# Protoboard.net
KiCad netlist of a schematic drawn in EAGLE
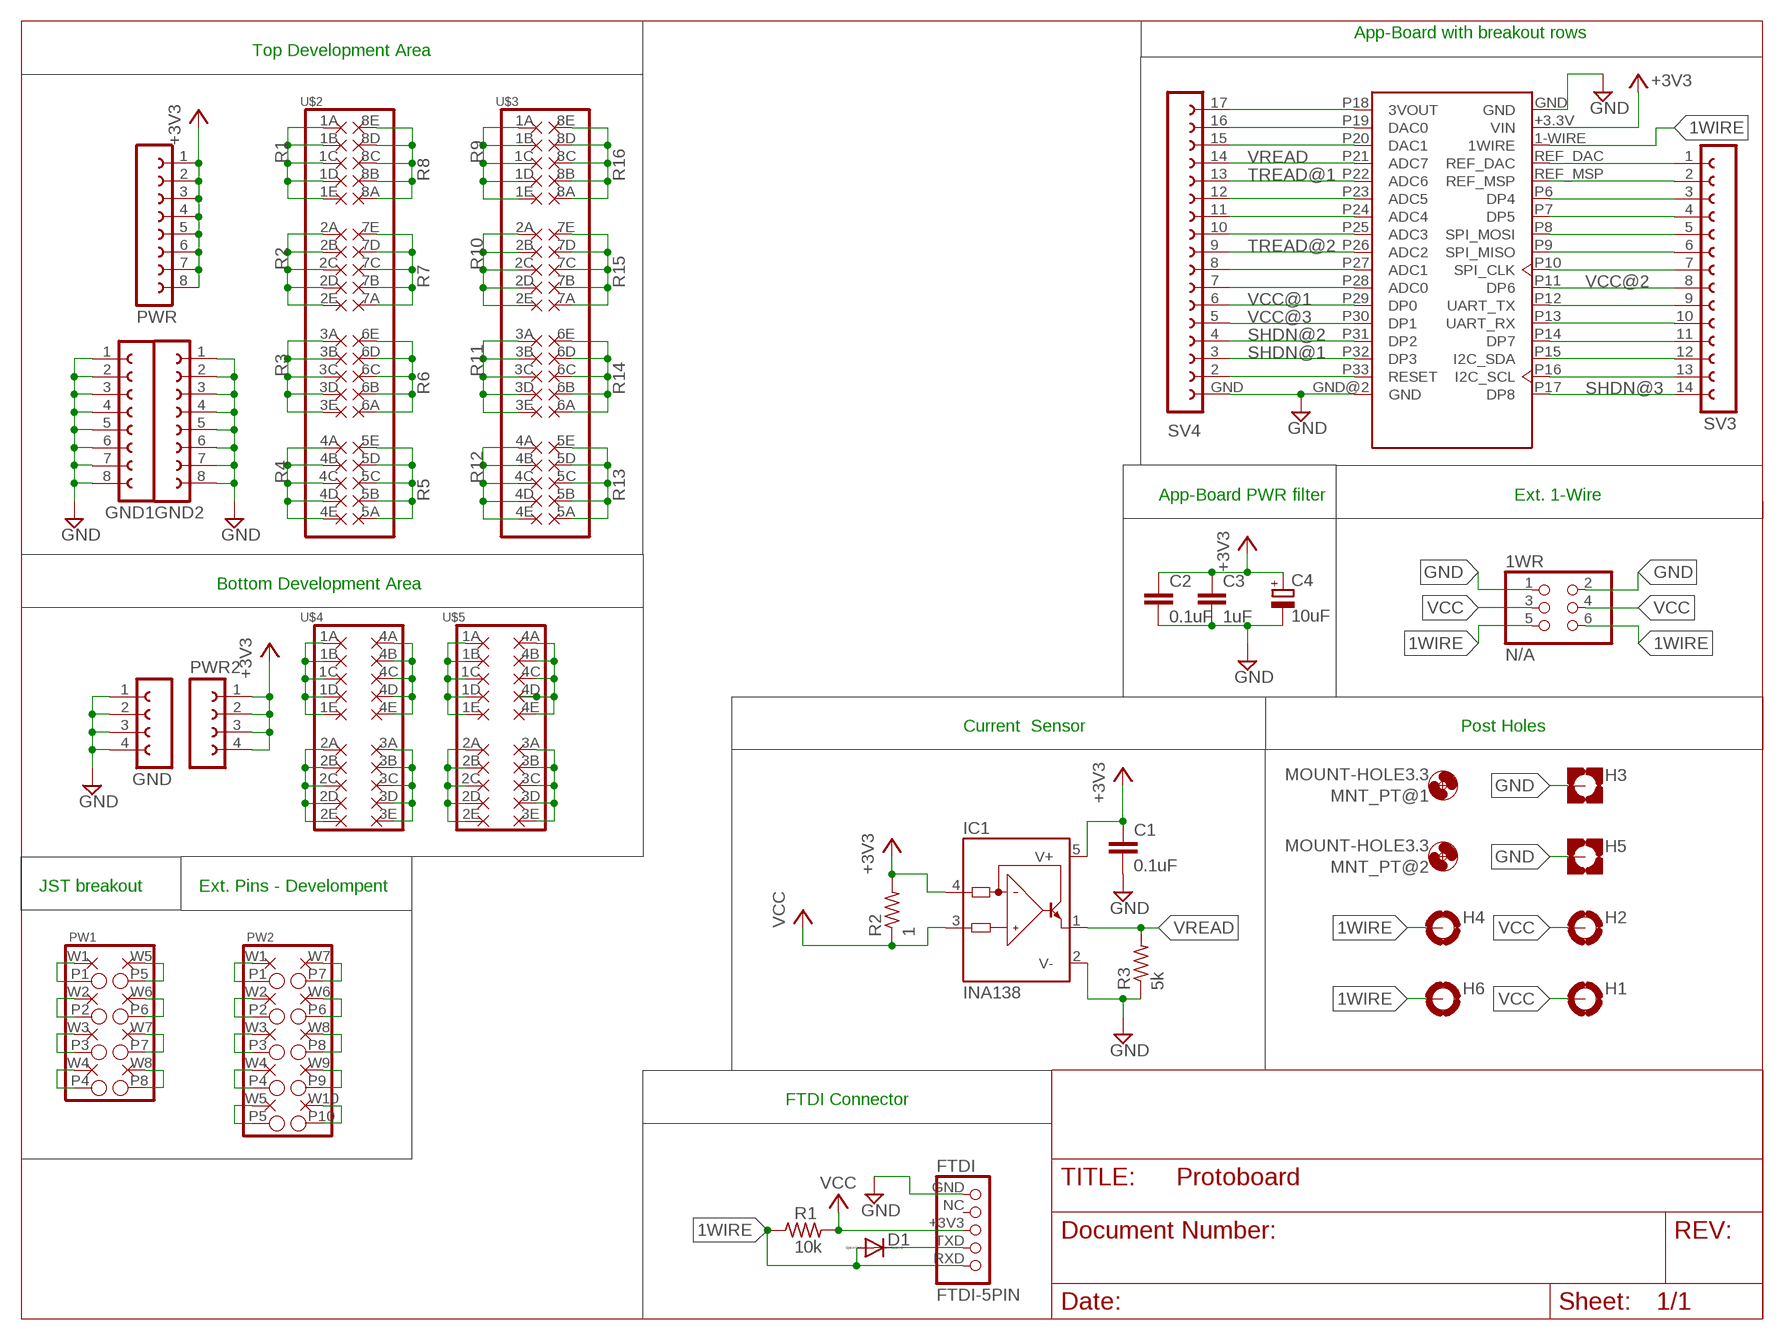
[diagram p0: schematic, sheet 1]

(export (version "E")
  (design (tool "Eeschema 10.0.6"))
  (components
    (comp (ref "1WR")
      (value "N/A")
      (footprint "eagle-import:2X03")
      (libsource (lib "eagle-import") (part "PINHD-2X3"))
    )
    (comp (ref "C1")
      (value "0.1uF")
      (footprint "eagle-import:C0603")
      (libsource (lib "eagle-import") (part "C-EUC0603"))
    )
    (comp (ref "C2")
      (value "0.1uF")
      (footprint "eagle-import:C0603")
      (libsource (lib "eagle-import") (part "C-EUC0603"))
    )
    (comp (ref "C3")
      (value "1uF")
      (footprint "eagle-import:C0603")
      (libsource (lib "eagle-import") (part "C-EUC0603"))
    )
    (comp (ref "C4")
      (value "10uF")
      (footprint "eagle-import:SMC_B")
      (libsource (lib "eagle-import") (part "CPOL-EUSMCB"))
    )
    (comp (ref "D1")
      (value "1N4148DO35-7")
      (footprint "eagle-import:DO35-7")
      (libsource (lib "eagle-import") (part "1N4148DO35-7"))
    )
    (comp (ref "FTDI")
      (value "FTDI-5PIN")
      (footprint "eagle-import:1X05")
      (libsource (lib "eagle-import") (part "FTDI-5PIN"))
    )
    (comp (ref "GND")
      (value "FE04-1-GND")
      (footprint "eagle-import:FE04-GND")
      (libsource (lib "eagle-import") (part "FE04-1-GND"))
    )
    (comp (ref "GND1")
      (value "FE08-1-GND")
      (footprint "eagle-import:FE08-GND")
      (libsource (lib "eagle-import") (part "FE08-1-GND"))
    )
    (comp (ref "GND2")
      (value "FE08-1-GND")
      (footprint "eagle-import:FE08-GND")
      (libsource (lib "eagle-import") (part "FE08-1-GND"))
    )
    (comp (ref "H1")
      (value "MOUNT-PAD-ROUND3.3")
      (footprint "eagle-import:3,3-PAD")
      (libsource (lib "eagle-import") (part "MOUNT-PAD-ROUND3.3"))
    )
    (comp (ref "H2")
      (value "MOUNT-PAD-ROUND3.3")
      (footprint "eagle-import:3,3-PAD")
      (libsource (lib "eagle-import") (part "MOUNT-PAD-ROUND3.3"))
    )
    (comp (ref "H3")
      (value "MOUNT-PAD-SQUARE3.3")
      (footprint "eagle-import:3,3-PAD-SQUARE")
      (libsource (lib "eagle-import") (part "MOUNT-PAD-SQUARE3.3"))
    )
    (comp (ref "H4")
      (value "MOUNT-PAD-ROUND3.3")
      (footprint "eagle-import:3,3-PAD")
      (libsource (lib "eagle-import") (part "MOUNT-PAD-ROUND3.3"))
    )
    (comp (ref "H5")
      (value "MOUNT-PAD-SQUARE3.3")
      (footprint "eagle-import:3,3-PAD-SQUARE")
      (libsource (lib "eagle-import") (part "MOUNT-PAD-SQUARE3.3"))
    )
    (comp (ref "H6")
      (value "MOUNT-PAD-ROUND3.3")
      (footprint "eagle-import:3,3-PAD")
      (libsource (lib "eagle-import") (part "MOUNT-PAD-ROUND3.3"))
    )
    (comp (ref "IC1")
      (value "INA138")
      (footprint "eagle-import:SOT23-5")
      (fields (field (name "MF") "TEXAS INSTRUMENTS") (field (name "MPN") "INA138NA/250"))
      (libsource (lib "eagle-import") (part "INA138"))
    )
    (comp (ref "MNT_PT@1")
      (value "MOUNT-HOLE3.3")
      (footprint "eagle-import:3,3")
      (libsource (lib "eagle-import") (part "MOUNT-HOLE3.3"))
    )
    (comp (ref "MNT_PT@2")
      (value "MOUNT-HOLE3.3")
      (footprint "eagle-import:3,3")
      (libsource (lib "eagle-import") (part "MOUNT-HOLE3.3"))
    )
    (comp (ref "PW1")
      (value "PIN-WIRE-2X8")
      (footprint "eagle-import:2X8")
      (libsource (lib "eagle-import") (part "PIN-WIRE-2X8"))
    )
    (comp (ref "PW2")
      (value "PIN-WIRE-2X10")
      (footprint "eagle-import:2X10")
      (libsource (lib "eagle-import") (part "PIN-WIRE-2X10"))
    )
    (comp (ref "PWR")
      (value "FE08-1")
      (footprint "eagle-import:FE08")
      (libsource (lib "eagle-import") (part "FE08-1"))
    )
    (comp (ref "PWR2")
      (value "FE04-1")
      (footprint "eagle-import:FE04-1")
      (libsource (lib "eagle-import") (part "FE04-1"))
    )
    (comp (ref "R1")
      (value "10k")
      (footprint "eagle-import:0204_5")
      (libsource (lib "eagle-import") (part "R-US_0204/5"))
    )
    (comp (ref "R2")
      (value "1")
      (footprint "eagle-import:R0603")
      (libsource (lib "eagle-import") (part "R-US_R0603"))
    )
    (comp (ref "R3")
      (value "5k")
      (footprint "eagle-import:R0805")
      (libsource (lib "eagle-import") (part "R-US_R0805"))
    )
    (comp (ref "SV3")
      (value "FE14-1_ABBO")
      (footprint "eagle-import:FE14-1_ABBO")
      (libsource (lib "eagle-import") (part "FE14-1_ABBO"))
    )
    (comp (ref "SV4")
      (value "FE17-1_ABBO")
      (footprint "eagle-import:FE17-1_ABBO")
      (libsource (lib "eagle-import") (part "FE17-1_ABBO"))
    )
    (comp (ref "U$1")
      (value "App-Board 1.2/1.3")
      (footprint "eagle-import:APPCORE_RECEIVER")
      (libsource (lib "eagle-import") (part "APP_CORE"))
    )
    (comp (ref "U$2")
      (value "PROTO-5X8")
      (footprint "eagle-import:PROTO-5X08")
      (libsource (lib "eagle-import") (part "PROTO-5X8"))
    )
    (comp (ref "U$3")
      (value "PROTO-5X8")
      (footprint "eagle-import:PROTO-5X08")
      (libsource (lib "eagle-import") (part "PROTO-5X8"))
    )
    (comp (ref "U$4")
      (value "PROTO-4X5")
      (footprint "eagle-import:PROTO-4X05")
      (libsource (lib "eagle-import") (part "PROTO-4X5"))
    )
    (comp (ref "U$5")
      (value "PROTO-4X5")
      (footprint "eagle-import:PROTO-4X05")
      (libsource (lib "eagle-import") (part "PROTO-4X5"))
    )
  )
  (nets
    (net (code "1") (name "+3V3") (class "Default")
      (node (ref "C1") (pin "1") (pinfunction "1_1") (pintype "passive"))
      (node (ref "C2") (pin "1") (pinfunction "1_1") (pintype "passive"))
      (node (ref "C3") (pin "1") (pinfunction "1_1") (pintype "passive"))
      (node (ref "C4") (pin "+") (pinfunction "+_+") (pintype "passive"))
      (node (ref "IC1") (pin "4") (pinfunction "IN-_4") (pintype "input"))
      (node (ref "IC1") (pin "5") (pinfunction "V+_5") (pintype "power_in"))
      (node (ref "PWR") (pin "1") (pinfunction "1_1") (pintype "passive"))
      (node (ref "PWR") (pin "2") (pinfunction "2_2") (pintype "passive"))
      (node (ref "PWR") (pin "3") (pinfunction "3_3") (pintype "passive"))
      (node (ref "PWR") (pin "4") (pinfunction "4_4") (pintype "passive"))
      (node (ref "PWR") (pin "5") (pinfunction "5_5") (pintype "passive"))
      (node (ref "PWR") (pin "6") (pinfunction "6_6") (pintype "passive"))
      (node (ref "PWR") (pin "7") (pinfunction "7_7") (pintype "passive"))
      (node (ref "PWR") (pin "8") (pinfunction "8_8") (pintype "passive"))
      (node (ref "PWR2") (pin "1") (pinfunction "1_1") (pintype "passive"))
      (node (ref "PWR2") (pin "2") (pinfunction "2_2") (pintype "passive"))
      (node (ref "PWR2") (pin "3") (pinfunction "3_3") (pintype "passive"))
      (node (ref "PWR2") (pin "4") (pinfunction "4_4") (pintype "passive"))
      (node (ref "R2") (pin "2") (pinfunction "2_2") (pintype "passive"))
      (node (ref "U$1") (pin "+3.3V") (pinfunction "VIN_+3.3V") (pintype "power_in"))
    )
    (net (code "2") (name "/R1") (class "Default")
      (node (ref "U$2") (pin "1A") (pinfunction "1A_1A") (pintype "passive"))
      (node (ref "U$2") (pin "1B") (pinfunction "1B_1B") (pintype "passive"))
      (node (ref "U$2") (pin "1C") (pinfunction "1C_1C") (pintype "passive"))
      (node (ref "U$2") (pin "1D") (pinfunction "1D_1D") (pintype "passive"))
      (node (ref "U$2") (pin "1E") (pinfunction "1E_1E") (pintype "passive"))
    )
    (net (code "3") (name "/R2") (class "Default")
      (node (ref "U$2") (pin "2A") (pinfunction "2A_2A") (pintype "passive"))
      (node (ref "U$2") (pin "2B") (pinfunction "2B_2B") (pintype "passive"))
      (node (ref "U$2") (pin "2C") (pinfunction "2C_2C") (pintype "passive"))
      (node (ref "U$2") (pin "2D") (pinfunction "2D_2D") (pintype "passive"))
      (node (ref "U$2") (pin "2E") (pinfunction "2E_2E") (pintype "passive"))
    )
    (net (code "4") (name "/R3") (class "Default")
      (node (ref "U$2") (pin "3A") (pinfunction "3A_3A") (pintype "passive"))
      (node (ref "U$2") (pin "3B") (pinfunction "3B_3B") (pintype "passive"))
      (node (ref "U$2") (pin "3C") (pinfunction "3C_3C") (pintype "passive"))
      (node (ref "U$2") (pin "3D") (pinfunction "3D_3D") (pintype "passive"))
      (node (ref "U$2") (pin "3E") (pinfunction "3E_3E") (pintype "passive"))
    )
    (net (code "5") (name "/R4") (class "Default")
      (node (ref "U$2") (pin "4A") (pinfunction "4A_4A") (pintype "passive"))
      (node (ref "U$2") (pin "4B") (pinfunction "4B_4B") (pintype "passive"))
      (node (ref "U$2") (pin "4C") (pinfunction "4C_4C") (pintype "passive"))
      (node (ref "U$2") (pin "4D") (pinfunction "4D_4D") (pintype "passive"))
      (node (ref "U$2") (pin "4E") (pinfunction "4E_4E") (pintype "passive"))
    )
    (net (code "6") (name "/R5") (class "Default")
      (node (ref "U$2") (pin "5A") (pinfunction "5A_5A") (pintype "passive"))
      (node (ref "U$2") (pin "5B") (pinfunction "5B_5B") (pintype "passive"))
      (node (ref "U$2") (pin "5C") (pinfunction "5C_5C") (pintype "passive"))
      (node (ref "U$2") (pin "5D") (pinfunction "5D_5D") (pintype "passive"))
      (node (ref "U$2") (pin "5E") (pinfunction "5E_5E") (pintype "passive"))
    )
    (net (code "7") (name "/R6") (class "Default")
      (node (ref "U$2") (pin "6A") (pinfunction "6A_6A") (pintype "passive"))
      (node (ref "U$2") (pin "6B") (pinfunction "6B_6B") (pintype "passive"))
      (node (ref "U$2") (pin "6C") (pinfunction "6C_6C") (pintype "passive"))
      (node (ref "U$2") (pin "6D") (pinfunction "6D_6D") (pintype "passive"))
      (node (ref "U$2") (pin "6E") (pinfunction "6E_6E") (pintype "passive"))
    )
    (net (code "8") (name "/R7") (class "Default")
      (node (ref "U$2") (pin "7A") (pinfunction "7A_7A") (pintype "passive"))
      (node (ref "U$2") (pin "7B") (pinfunction "7B_7B") (pintype "passive"))
      (node (ref "U$2") (pin "7C") (pinfunction "7C_7C") (pintype "passive"))
      (node (ref "U$2") (pin "7D") (pinfunction "7D_7D") (pintype "passive"))
      (node (ref "U$2") (pin "7E") (pinfunction "7E_7E") (pintype "passive"))
    )
    (net (code "9") (name "/R8") (class "Default")
      (node (ref "U$2") (pin "8A") (pinfunction "8A_8A") (pintype "passive"))
      (node (ref "U$2") (pin "8B") (pinfunction "8B_8B") (pintype "passive"))
      (node (ref "U$2") (pin "8C") (pinfunction "8C_8C") (pintype "passive"))
      (node (ref "U$2") (pin "8D") (pinfunction "8D_8D") (pintype "passive"))
      (node (ref "U$2") (pin "8E") (pinfunction "8E_8E") (pintype "passive"))
    )
    (net (code "10") (name "/R9") (class "Default")
      (node (ref "U$3") (pin "1A") (pinfunction "1A_1A") (pintype "passive"))
      (node (ref "U$3") (pin "1B") (pinfunction "1B_1B") (pintype "passive"))
      (node (ref "U$3") (pin "1C") (pinfunction "1C_1C") (pintype "passive"))
      (node (ref "U$3") (pin "1D") (pinfunction "1D_1D") (pintype "passive"))
      (node (ref "U$3") (pin "1E") (pinfunction "1E_1E") (pintype "passive"))
    )
    (net (code "11") (name "/R10") (class "Default")
      (node (ref "U$3") (pin "2A") (pinfunction "2A_2A") (pintype "passive"))
      (node (ref "U$3") (pin "2B") (pinfunction "2B_2B") (pintype "passive"))
      (node (ref "U$3") (pin "2C") (pinfunction "2C_2C") (pintype "passive"))
      (node (ref "U$3") (pin "2D") (pinfunction "2D_2D") (pintype "passive"))
      (node (ref "U$3") (pin "2E") (pinfunction "2E_2E") (pintype "passive"))
    )
    (net (code "12") (name "/R11") (class "Default")
      (node (ref "U$3") (pin "3A") (pinfunction "3A_3A") (pintype "passive"))
      (node (ref "U$3") (pin "3B") (pinfunction "3B_3B") (pintype "passive"))
      (node (ref "U$3") (pin "3C") (pinfunction "3C_3C") (pintype "passive"))
      (node (ref "U$3") (pin "3D") (pinfunction "3D_3D") (pintype "passive"))
      (node (ref "U$3") (pin "3E") (pinfunction "3E_3E") (pintype "passive"))
    )
    (net (code "13") (name "/R12") (class "Default")
      (node (ref "U$3") (pin "4A") (pinfunction "4A_4A") (pintype "passive"))
      (node (ref "U$3") (pin "4B") (pinfunction "4B_4B") (pintype "passive"))
      (node (ref "U$3") (pin "4C") (pinfunction "4C_4C") (pintype "passive"))
      (node (ref "U$3") (pin "4D") (pinfunction "4D_4D") (pintype "passive"))
      (node (ref "U$3") (pin "4E") (pinfunction "4E_4E") (pintype "passive"))
    )
    (net (code "14") (name "/R13") (class "Default")
      (node (ref "U$3") (pin "5A") (pinfunction "5A_5A") (pintype "passive"))
      (node (ref "U$3") (pin "5B") (pinfunction "5B_5B") (pintype "passive"))
      (node (ref "U$3") (pin "5C") (pinfunction "5C_5C") (pintype "passive"))
      (node (ref "U$3") (pin "5D") (pinfunction "5D_5D") (pintype "passive"))
      (node (ref "U$3") (pin "5E") (pinfunction "5E_5E") (pintype "passive"))
    )
    (net (code "15") (name "/R14") (class "Default")
      (node (ref "U$3") (pin "6A") (pinfunction "6A_6A") (pintype "passive"))
      (node (ref "U$3") (pin "6B") (pinfunction "6B_6B") (pintype "passive"))
      (node (ref "U$3") (pin "6C") (pinfunction "6C_6C") (pintype "passive"))
      (node (ref "U$3") (pin "6D") (pinfunction "6D_6D") (pintype "passive"))
      (node (ref "U$3") (pin "6E") (pinfunction "6E_6E") (pintype "passive"))
    )
    (net (code "16") (name "/R15") (class "Default")
      (node (ref "U$3") (pin "7A") (pinfunction "7A_7A") (pintype "passive"))
      (node (ref "U$3") (pin "7B") (pinfunction "7B_7B") (pintype "passive"))
      (node (ref "U$3") (pin "7C") (pinfunction "7C_7C") (pintype "passive"))
      (node (ref "U$3") (pin "7D") (pinfunction "7D_7D") (pintype "passive"))
      (node (ref "U$3") (pin "7E") (pinfunction "7E_7E") (pintype "passive"))
    )
    (net (code "17") (name "/R16") (class "Default")
      (node (ref "U$3") (pin "8A") (pinfunction "8A_8A") (pintype "passive"))
      (node (ref "U$3") (pin "8B") (pinfunction "8B_8B") (pintype "passive"))
      (node (ref "U$3") (pin "8C") (pinfunction "8C_8C") (pintype "passive"))
      (node (ref "U$3") (pin "8D") (pinfunction "8D_8D") (pintype "passive"))
      (node (ref "U$3") (pin "8E") (pinfunction "8E_8E") (pintype "passive"))
    )
    (net (code "18") (name "/SHDN@1") (class "Default")
      (node (ref "SV4") (pin "3") (pinfunction "3_3") (pintype "passive"))
      (node (ref "U$1") (pin "P32") (pinfunction "DP3_P32") (pintype "bidirectional"))
    )
    (net (code "19") (name "/SHDN@2") (class "Default")
      (node (ref "SV4") (pin "4") (pinfunction "4_4") (pintype "passive"))
      (node (ref "U$1") (pin "P31") (pinfunction "DP2_P31") (pintype "bidirectional"))
    )
    (net (code "20") (name "/SHDN@3") (class "Default")
      (node (ref "SV3") (pin "14") (pinfunction "14_14") (pintype "passive"))
      (node (ref "U$1") (pin "P17") (pinfunction "DP8_P17") (pintype "bidirectional"))
    )
    (net (code "21") (name "/TREAD@1") (class "Default")
      (node (ref "SV4") (pin "13") (pinfunction "13_13") (pintype "passive"))
      (node (ref "U$1") (pin "P22") (pinfunction "ADC6_P22") (pintype "input"))
    )
    (net (code "22") (name "/TREAD@2") (class "Default")
      (node (ref "SV4") (pin "9") (pinfunction "9_9") (pintype "passive"))
      (node (ref "U$1") (pin "P26") (pinfunction "ADC2_P26") (pintype "input"))
    )
    (net (code "23") (name "/VCC@1") (class "Default")
      (node (ref "SV4") (pin "6") (pinfunction "6_6") (pintype "passive"))
      (node (ref "U$1") (pin "P29") (pinfunction "DP0_P29") (pintype "bidirectional"))
    )
    (net (code "24") (name "/VCC@2") (class "Default")
      (node (ref "SV3") (pin "8") (pinfunction "8_8") (pintype "passive"))
      (node (ref "U$1") (pin "P11") (pinfunction "DP6_P11") (pintype "bidirectional"))
    )
    (net (code "25") (name "/VCC@3") (class "Default")
      (node (ref "SV4") (pin "5") (pinfunction "5_5") (pintype "passive"))
      (node (ref "U$1") (pin "P30") (pinfunction "DP1_P30") (pintype "bidirectional"))
    )
    (net (code "26") (name "1WIRE") (class "Default")
      (node (ref "1WR") (pin "5") (pinfunction "5_5") (pintype "passive"))
      (node (ref "1WR") (pin "6") (pinfunction "6_6") (pintype "passive"))
      (node (ref "D1") (pin "A") (pinfunction "A_A") (pintype "passive"))
      (node (ref "FTDI") (pin "RXD") (pinfunction "RXD_RXD") (pintype "input"))
      (node (ref "H4") (pin "B3,3") (pinfunction "MOUNT_B3,3") (pintype "passive"))
      (node (ref "H6") (pin "B3,3") (pinfunction "MOUNT_B3,3") (pintype "passive"))
      (node (ref "R1") (pin "1") (pinfunction "1_1") (pintype "passive"))
      (node (ref "U$1") (pin "1-WIRE") (pinfunction "1WIRE_1-WIRE") (pintype "bidirectional"))
    )
    (net (code "27") (name "GND") (class "Default")
      (node (ref "1WR") (pin "1") (pinfunction "1_1") (pintype "passive"))
      (node (ref "1WR") (pin "2") (pinfunction "2_2") (pintype "passive"))
      (node (ref "C1") (pin "2") (pinfunction "2_2") (pintype "passive"))
      (node (ref "C2") (pin "2") (pinfunction "2_2") (pintype "passive"))
      (node (ref "C3") (pin "2") (pinfunction "2_2") (pintype "passive"))
      (node (ref "C4") (pin "-") (pinfunction "-_-") (pintype "passive"))
      (node (ref "FTDI") (pin "GND") (pinfunction "GND_GND") (pintype "power_in"))
      (node (ref "GND") (pin "1") (pinfunction "1_1") (pintype "passive"))
      (node (ref "GND") (pin "2") (pinfunction "2_2") (pintype "passive"))
      (node (ref "GND") (pin "3") (pinfunction "3_3") (pintype "passive"))
      (node (ref "GND") (pin "4") (pinfunction "4_4") (pintype "passive"))
      (node (ref "GND1") (pin "1") (pinfunction "1_1") (pintype "passive"))
      (node (ref "GND1") (pin "2") (pinfunction "2_2") (pintype "passive"))
      (node (ref "GND1") (pin "3") (pinfunction "3_3") (pintype "passive"))
      (node (ref "GND1") (pin "4") (pinfunction "4_4") (pintype "passive"))
      (node (ref "GND1") (pin "5") (pinfunction "5_5") (pintype "passive"))
      (node (ref "GND1") (pin "6") (pinfunction "6_6") (pintype "passive"))
      (node (ref "GND1") (pin "7") (pinfunction "7_7") (pintype "passive"))
      (node (ref "GND1") (pin "8") (pinfunction "8_8") (pintype "passive"))
      (node (ref "GND2") (pin "1") (pinfunction "1_1") (pintype "passive"))
      (node (ref "GND2") (pin "2") (pinfunction "2_2") (pintype "passive"))
      (node (ref "GND2") (pin "3") (pinfunction "3_3") (pintype "passive"))
      (node (ref "GND2") (pin "4") (pinfunction "4_4") (pintype "passive"))
      (node (ref "GND2") (pin "5") (pinfunction "5_5") (pintype "passive"))
      (node (ref "GND2") (pin "6") (pinfunction "6_6") (pintype "passive"))
      (node (ref "GND2") (pin "7") (pinfunction "7_7") (pintype "passive"))
      (node (ref "GND2") (pin "8") (pinfunction "8_8") (pintype "passive"))
      (node (ref "H3") (pin "B3,3") (pinfunction "MOUNT_B3,3") (pintype "passive"))
      (node (ref "H5") (pin "B3,3") (pinfunction "MOUNT_B3,3") (pintype "passive"))
      (node (ref "IC1") (pin "2") (pinfunction "V-_2") (pintype "power_in"))
      (node (ref "R3") (pin "1") (pinfunction "1_1") (pintype "passive"))
      (node (ref "SV4") (pin "GND") (pinfunction "GND_GND") (pintype "power_in"))
      (node (ref "U$1") (pin "GND") (pinfunction "GND_GND") (pintype "power_in"))
      (node (ref "U$1") (pin "GND@2") (pinfunction "GND_GND@2") (pintype "power_in"))
    )
    (net (code "28") (name "Net-(D1-PadC)") (class "Default")
      (node (ref "D1") (pin "C") (pinfunction "C_C") (pintype "passive"))
      (node (ref "FTDI") (pin "TXD") (pinfunction "TXD_TXD") (pintype "output"))
    )
    (net (code "29") (name "Net-(PW1-P$1)") (class "Default")
      (node (ref "PW1") (pin "P1") (pinfunction "P$1_P1") (pintype "passive"))
      (node (ref "PW1") (pin "W1") (pinfunction "W$1_W1") (pintype "passive"))
    )
    (net (code "30") (name "Net-(PW1-P$2)") (class "Default")
      (node (ref "PW1") (pin "P2") (pinfunction "P$2_P2") (pintype "passive"))
      (node (ref "PW1") (pin "W2") (pinfunction "W$2_W2") (pintype "passive"))
    )
    (net (code "31") (name "Net-(PW1-P$3)") (class "Default")
      (node (ref "PW1") (pin "P3") (pinfunction "P$3_P3") (pintype "passive"))
      (node (ref "PW1") (pin "W3") (pinfunction "W$3_W3") (pintype "passive"))
    )
    (net (code "32") (name "Net-(PW1-P$4)") (class "Default")
      (node (ref "PW1") (pin "P4") (pinfunction "P$4_P4") (pintype "passive"))
      (node (ref "PW1") (pin "W4") (pinfunction "W$4_W4") (pintype "passive"))
    )
    (net (code "33") (name "Net-(PW1-P$5)") (class "Default")
      (node (ref "PW1") (pin "P5") (pinfunction "P$5_P5") (pintype "passive"))
      (node (ref "PW1") (pin "W5") (pinfunction "W$5_W5") (pintype "passive"))
    )
    (net (code "34") (name "Net-(PW1-P$6)") (class "Default")
      (node (ref "PW1") (pin "P6") (pinfunction "P$6_P6") (pintype "passive"))
      (node (ref "PW1") (pin "W6") (pinfunction "W$6_W6") (pintype "passive"))
    )
    (net (code "35") (name "Net-(PW1-P$7)") (class "Default")
      (node (ref "PW1") (pin "P7") (pinfunction "P$7_P7") (pintype "passive"))
      (node (ref "PW1") (pin "W7") (pinfunction "W$7_W7") (pintype "passive"))
    )
    (net (code "36") (name "Net-(PW1-P$8)") (class "Default")
      (node (ref "PW1") (pin "P8") (pinfunction "P$8_P8") (pintype "passive"))
      (node (ref "PW1") (pin "W8") (pinfunction "W$8_W8") (pintype "passive"))
    )
    (net (code "37") (name "Net-(PW2-P$1)") (class "Default")
      (node (ref "PW2") (pin "P1") (pinfunction "P$1_P1") (pintype "passive"))
      (node (ref "PW2") (pin "W1") (pinfunction "W$1_W1") (pintype "passive"))
    )
    (net (code "38") (name "Net-(PW2-P$2)") (class "Default")
      (node (ref "PW2") (pin "P2") (pinfunction "P$2_P2") (pintype "passive"))
      (node (ref "PW2") (pin "W2") (pinfunction "W$2_W2") (pintype "passive"))
    )
    (net (code "39") (name "Net-(PW2-P$3)") (class "Default")
      (node (ref "PW2") (pin "P3") (pinfunction "P$3_P3") (pintype "passive"))
      (node (ref "PW2") (pin "W3") (pinfunction "W$3_W3") (pintype "passive"))
    )
    (net (code "40") (name "Net-(PW2-P$4)") (class "Default")
      (node (ref "PW2") (pin "P4") (pinfunction "P$4_P4") (pintype "passive"))
      (node (ref "PW2") (pin "W4") (pinfunction "W$4_W4") (pintype "passive"))
    )
    (net (code "41") (name "Net-(PW2-P$5)") (class "Default")
      (node (ref "PW2") (pin "P5") (pinfunction "P$5_P5") (pintype "passive"))
      (node (ref "PW2") (pin "W5") (pinfunction "W$5_W5") (pintype "passive"))
    )
    (net (code "42") (name "Net-(PW2-P$6)") (class "Default")
      (node (ref "PW2") (pin "P6") (pinfunction "P$6_P6") (pintype "passive"))
      (node (ref "PW2") (pin "W6") (pinfunction "W$6_W6") (pintype "passive"))
    )
    (net (code "43") (name "Net-(PW2-P$7)") (class "Default")
      (node (ref "PW2") (pin "P7") (pinfunction "P$7_P7") (pintype "passive"))
      (node (ref "PW2") (pin "W7") (pinfunction "W$7_W7") (pintype "passive"))
    )
    (net (code "44") (name "Net-(PW2-P$8)") (class "Default")
      (node (ref "PW2") (pin "P8") (pinfunction "P$8_P8") (pintype "passive"))
      (node (ref "PW2") (pin "W8") (pinfunction "W$8_W8") (pintype "passive"))
    )
    (net (code "45") (name "Net-(PW2-P$9)") (class "Default")
      (node (ref "PW2") (pin "P9") (pinfunction "P$9_P9") (pintype "passive"))
      (node (ref "PW2") (pin "W9") (pinfunction "W$9_W9") (pintype "passive"))
    )
    (net (code "46") (name "Net-(PW2-P$10)") (class "Default")
      (node (ref "PW2") (pin "P10") (pinfunction "P$10_P10") (pintype "passive"))
      (node (ref "PW2") (pin "W10") (pinfunction "W$10_W10") (pintype "passive"))
    )
    (net (code "47") (name "Net-(SV3-Pad1)") (class "Default")
      (node (ref "SV3") (pin "1") (pinfunction "1_1") (pintype "passive"))
      (node (ref "U$1") (pin "REF_DAC") (pinfunction "REF_DAC_REF_DAC") (pintype "input"))
    )
    (net (code "48") (name "Net-(SV3-Pad2)") (class "Default")
      (node (ref "SV3") (pin "2") (pinfunction "2_2") (pintype "passive"))
      (node (ref "U$1") (pin "REF_MSP") (pinfunction "REF_MSP_REF_MSP") (pintype "input"))
    )
    (net (code "49") (name "Net-(U$1-3VOUT)") (class "Default")
      (node (ref "SV4") (pin "17") (pinfunction "17_17") (pintype "passive"))
      (node (ref "U$1") (pin "P18") (pinfunction "3VOUT_P18") (pintype "output"))
    )
    (net (code "50") (name "Net-(U$1-ADC0)") (class "Default")
      (node (ref "SV4") (pin "7") (pinfunction "7_7") (pintype "passive"))
      (node (ref "U$1") (pin "P28") (pinfunction "ADC0_P28") (pintype "input"))
    )
    (net (code "51") (name "Net-(U$1-ADC1)") (class "Default")
      (node (ref "SV4") (pin "8") (pinfunction "8_8") (pintype "passive"))
      (node (ref "U$1") (pin "P27") (pinfunction "ADC1_P27") (pintype "input"))
    )
    (net (code "52") (name "Net-(U$1-ADC3)") (class "Default")
      (node (ref "SV4") (pin "10") (pinfunction "10_10") (pintype "passive"))
      (node (ref "U$1") (pin "P25") (pinfunction "ADC3_P25") (pintype "input"))
    )
    (net (code "53") (name "Net-(U$1-ADC4)") (class "Default")
      (node (ref "SV4") (pin "11") (pinfunction "11_11") (pintype "passive"))
      (node (ref "U$1") (pin "P24") (pinfunction "ADC4_P24") (pintype "input"))
    )
    (net (code "54") (name "Net-(U$1-ADC5)") (class "Default")
      (node (ref "SV4") (pin "12") (pinfunction "12_12") (pintype "passive"))
      (node (ref "U$1") (pin "P23") (pinfunction "ADC5_P23") (pintype "input"))
    )
    (net (code "55") (name "Net-(U$1-DAC0)") (class "Default")
      (node (ref "SV4") (pin "16") (pinfunction "16_16") (pintype "passive"))
      (node (ref "U$1") (pin "P19") (pinfunction "DAC0_P19") (pintype "bidirectional"))
    )
    (net (code "56") (name "Net-(U$1-DAC1)") (class "Default")
      (node (ref "SV4") (pin "15") (pinfunction "15_15") (pintype "passive"))
      (node (ref "U$1") (pin "P20") (pinfunction "DAC1_P20") (pintype "bidirectional"))
    )
    (net (code "57") (name "Net-(U$1-DP4)") (class "Default")
      (node (ref "SV3") (pin "3") (pinfunction "3_3") (pintype "passive"))
      (node (ref "U$1") (pin "P6") (pinfunction "DP4_P6") (pintype "bidirectional"))
    )
    (net (code "58") (name "Net-(U$1-DP5)") (class "Default")
      (node (ref "SV3") (pin "4") (pinfunction "4_4") (pintype "passive"))
      (node (ref "U$1") (pin "P7") (pinfunction "DP5_P7") (pintype "bidirectional"))
    )
    (net (code "59") (name "Net-(U$1-DP7)") (class "Default")
      (node (ref "SV3") (pin "11") (pinfunction "11_11") (pintype "passive"))
      (node (ref "U$1") (pin "P14") (pinfunction "DP7_P14") (pintype "bidirectional"))
    )
    (net (code "60") (name "Net-(U$1-I2C_SCL)") (class "Default")
      (node (ref "SV3") (pin "13") (pinfunction "13_13") (pintype "passive"))
      (node (ref "U$1") (pin "P16") (pinfunction "I2C_SCL_P16") (pintype "bidirectional"))
    )
    (net (code "61") (name "Net-(U$1-I2C_SDA)") (class "Default")
      (node (ref "SV3") (pin "12") (pinfunction "12_12") (pintype "passive"))
      (node (ref "U$1") (pin "P15") (pinfunction "I2C_SDA_P15") (pintype "bidirectional"))
    )
    (net (code "62") (name "Net-(U$1-RESET)") (class "Default")
      (node (ref "SV4") (pin "2") (pinfunction "2_2") (pintype "passive"))
      (node (ref "U$1") (pin "P33") (pinfunction "RESET_P33") (pintype "bidirectional"))
    )
    (net (code "63") (name "Net-(U$1-SPI_CLK)") (class "Default")
      (node (ref "SV3") (pin "7") (pinfunction "7_7") (pintype "passive"))
      (node (ref "U$1") (pin "P10") (pinfunction "SPI_CLK_P10") (pintype "bidirectional"))
    )
    (net (code "64") (name "Net-(U$1-SPI_MISO)") (class "Default")
      (node (ref "SV3") (pin "6") (pinfunction "6_6") (pintype "passive"))
      (node (ref "U$1") (pin "P9") (pinfunction "SPI_MISO_P9") (pintype "bidirectional"))
    )
    (net (code "65") (name "Net-(U$1-SPI_MOSI)") (class "Default")
      (node (ref "SV3") (pin "5") (pinfunction "5_5") (pintype "passive"))
      (node (ref "U$1") (pin "P8") (pinfunction "SPI_MOSI_P8") (pintype "bidirectional"))
    )
    (net (code "66") (name "Net-(U$1-UART_RX)") (class "Default")
      (node (ref "SV3") (pin "10") (pinfunction "10_10") (pintype "passive"))
      (node (ref "U$1") (pin "P13") (pinfunction "UART_RX_P13") (pintype "input"))
    )
    (net (code "67") (name "Net-(U$1-UART_TX)") (class "Default")
      (node (ref "SV3") (pin "9") (pinfunction "9_9") (pintype "passive"))
      (node (ref "U$1") (pin "P12") (pinfunction "UART_TX_P12") (pintype "output"))
    )
    (net (code "68") (name "Net-(U$4-Pad1A)") (class "Default")
      (node (ref "U$4") (pin "1A") (pinfunction "1A_1A") (pintype "passive"))
      (node (ref "U$4") (pin "1B") (pinfunction "1B_1B") (pintype "passive"))
      (node (ref "U$4") (pin "1C") (pinfunction "1C_1C") (pintype "passive"))
      (node (ref "U$4") (pin "1D") (pinfunction "1D_1D") (pintype "passive"))
      (node (ref "U$4") (pin "1E") (pinfunction "1E_1E") (pintype "passive"))
    )
    (net (code "69") (name "Net-(U$4-Pad2A)") (class "Default")
      (node (ref "U$4") (pin "2A") (pinfunction "2A_2A") (pintype "passive"))
      (node (ref "U$4") (pin "2B") (pinfunction "2B_2B") (pintype "passive"))
      (node (ref "U$4") (pin "2C") (pinfunction "2C_2C") (pintype "passive"))
      (node (ref "U$4") (pin "2D") (pinfunction "2D_2D") (pintype "passive"))
      (node (ref "U$4") (pin "2E") (pinfunction "2E_2E") (pintype "passive"))
    )
    (net (code "70") (name "Net-(U$4-Pad3A)") (class "Default")
      (node (ref "U$4") (pin "3A") (pinfunction "3A_3A") (pintype "passive"))
      (node (ref "U$4") (pin "3B") (pinfunction "3B_3B") (pintype "passive"))
      (node (ref "U$4") (pin "3C") (pinfunction "3C_3C") (pintype "passive"))
      (node (ref "U$4") (pin "3D") (pinfunction "3D_3D") (pintype "passive"))
      (node (ref "U$4") (pin "3E") (pinfunction "3E_3E") (pintype "passive"))
    )
    (net (code "71") (name "Net-(U$4-Pad4A)") (class "Default")
      (node (ref "U$4") (pin "4A") (pinfunction "4A_4A") (pintype "passive"))
      (node (ref "U$4") (pin "4B") (pinfunction "4B_4B") (pintype "passive"))
      (node (ref "U$4") (pin "4C") (pinfunction "4C_4C") (pintype "passive"))
      (node (ref "U$4") (pin "4D") (pinfunction "4D_4D") (pintype "passive"))
      (node (ref "U$4") (pin "4E") (pinfunction "4E_4E") (pintype "passive"))
    )
    (net (code "72") (name "Net-(U$5-Pad1A)") (class "Default")
      (node (ref "U$5") (pin "1A") (pinfunction "1A_1A") (pintype "passive"))
      (node (ref "U$5") (pin "1B") (pinfunction "1B_1B") (pintype "passive"))
      (node (ref "U$5") (pin "1C") (pinfunction "1C_1C") (pintype "passive"))
      (node (ref "U$5") (pin "1D") (pinfunction "1D_1D") (pintype "passive"))
      (node (ref "U$5") (pin "1E") (pinfunction "1E_1E") (pintype "passive"))
    )
    (net (code "73") (name "Net-(U$5-Pad2A)") (class "Default")
      (node (ref "U$5") (pin "2A") (pinfunction "2A_2A") (pintype "passive"))
      (node (ref "U$5") (pin "2B") (pinfunction "2B_2B") (pintype "passive"))
      (node (ref "U$5") (pin "2C") (pinfunction "2C_2C") (pintype "passive"))
      (node (ref "U$5") (pin "2D") (pinfunction "2D_2D") (pintype "passive"))
      (node (ref "U$5") (pin "2E") (pinfunction "2E_2E") (pintype "passive"))
    )
    (net (code "74") (name "Net-(U$5-Pad3A)") (class "Default")
      (node (ref "U$5") (pin "3A") (pinfunction "3A_3A") (pintype "passive"))
      (node (ref "U$5") (pin "3B") (pinfunction "3B_3B") (pintype "passive"))
      (node (ref "U$5") (pin "3C") (pinfunction "3C_3C") (pintype "passive"))
      (node (ref "U$5") (pin "3D") (pinfunction "3D_3D") (pintype "passive"))
      (node (ref "U$5") (pin "3E") (pinfunction "3E_3E") (pintype "passive"))
    )
    (net (code "75") (name "Net-(U$5-Pad4A)") (class "Default")
      (node (ref "U$5") (pin "4A") (pinfunction "4A_4A") (pintype "passive"))
      (node (ref "U$5") (pin "4B") (pinfunction "4B_4B") (pintype "passive"))
      (node (ref "U$5") (pin "4C") (pinfunction "4C_4C") (pintype "passive"))
      (node (ref "U$5") (pin "4D") (pinfunction "4D_4D") (pintype "passive"))
      (node (ref "U$5") (pin "4E") (pinfunction "4E_4E") (pintype "passive"))
    )
    (net (code "76") (name "VCC") (class "Default")
      (node (ref "1WR") (pin "3") (pinfunction "3_3") (pintype "passive"))
      (node (ref "1WR") (pin "4") (pinfunction "4_4") (pintype "passive"))
      (node (ref "FTDI") (pin "+3V3") (pinfunction "+3V3_+3V3") (pintype "power_in"))
      (node (ref "H1") (pin "B3,3") (pinfunction "MOUNT_B3,3") (pintype "passive"))
      (node (ref "H2") (pin "B3,3") (pinfunction "MOUNT_B3,3") (pintype "passive"))
      (node (ref "IC1") (pin "3") (pinfunction "IN+_3") (pintype "input"))
      (node (ref "R1") (pin "2") (pinfunction "2_2") (pintype "passive"))
      (node (ref "R2") (pin "1") (pinfunction "1_1") (pintype "passive"))
    )
    (net (code "77") (name "VREAD") (class "Default")
      (node (ref "IC1") (pin "1") (pinfunction "OUT_1") (pintype "output"))
      (node (ref "R3") (pin "2") (pinfunction "2_2") (pintype "passive"))
      (node (ref "SV4") (pin "14") (pinfunction "14_14") (pintype "passive"))
      (node (ref "U$1") (pin "P21") (pinfunction "ADC7_P21") (pintype "input"))
    )
    (net (code "78") (name "unconnected-(FTDI-PadNC)") (class "Default")
      (node (ref "FTDI") (pin "NC") (pinfunction "NC_NC") (pintype "no_connect"))
    )
  )
)
